# Door_Sensor_Schematic.net
KiCad netlist of a schematic drawn in Altium Designer
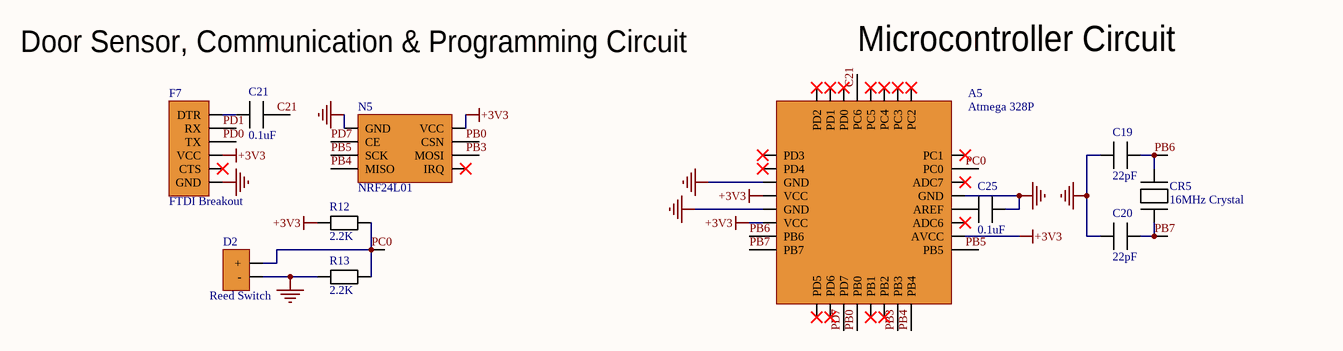
[diagram p0: Door Sensor Schematic.SchDoc]

(export (version "E")
  (design (tool "Eeschema 10.0.6"))
  (components
    (comp (ref "A5")
      (value "Atmega 328P")
      (footprint "ATMega328P")
      (description "IC MCU 8BIT 32KB FLASH 32TQFP")
      (fields
        (field (name "MANUFACTURER") "Microchip")
        (field (name "MANUFACTURER PART NUMBER") "ATMEGA328PB-AUR")
      )
      (libsource (lib "Schematic Library") (part "ATMEGA328PB-AUR"))
    )
    (comp (ref "C19")
      (value "22pF")
      (footprint "22pF Capacitor")
      (description "Cap Ceramic 22pF 50V C0G 5% SMD 0603 125C Paper T/R")
      (fields
        (field (name "MANUFACTURER") "Kyocera AVX")
        (field (name "MANUFACTURER PART NUMBER") "06035A220JAT2A")
      )
      (libsource (lib "Schematic Library") (part "06035A220JAT2A"))
    )
    (comp (ref "C20")
      (value "22pF")
      (footprint "22pF Capacitor")
      (description "Cap Ceramic 22pF 50V C0G 5% SMD 0603 125C Paper T/R")
      (fields
        (field (name "MANUFACTURER") "Kyocera AVX")
        (field (name "MANUFACTURER PART NUMBER") "06035A220JAT2A")
      )
      (libsource (lib "Schematic Library") (part "06035A220JAT2A"))
    )
    (comp (ref "C21")
      (value "0.1uF")
      (footprint "0.1uF Capacitor")
      (description "CAP CER 0.1UF 25V X7R 0603")
      (fields
        (field (name "MANUFACTURER") "Kyocera AVX")
        (field (name "MANUFACTURER PART NUMBER") "06033C104KAT4A")
      )
      (libsource (lib "Schematic Library") (part "06033C104KAT4A"))
    )
    (comp (ref "C25")
      (value "0.1uF")
      (footprint "0.1uF Capacitor")
      (description "CAP CER 0.1UF 25V X7R 0603")
      (fields
        (field (name "MANUFACTURER") "Kyocera AVX")
        (field (name "MANUFACTURER PART NUMBER") "06033C104KAT4A")
      )
      (libsource (lib "Schematic Library") (part "06033C104KAT4A"))
    )
    (comp (ref "CR5")
      (value "16MHz Crystal")
      (footprint "16MHz Crystal")
      (description "CRYSTAL 16.0000MHZ 20PF SMD")
      (fields
        (field (name "MANUFACTURER") "ECS International")
        (field (name "MANUFACTURER PART NUMBER") "ECS-160-20-3X-TR")
      )
      (libsource (lib "Schematic Library") (part "ECS-160-20-3X-TR"))
    )
    (comp (ref "D2")
      (value "Reed Switch")
      (footprint "Reed Switch")
      (description "Magnetic Door Switch Set")
      (fields (field (name "MANUFACTURER") "SparkFun") (field (name "MANUFACTURER PART NUMBER") "COM-13247"))
      (libsource (lib "Schematic Library") (part "COM-13247"))
    )
    (comp (ref "F7")
      (value "FTDI Breakout")
      (footprint "FTDI")
      (description "FTDI USB to TTL serial converter module")
      (libsource (lib "Schematic Library") (part "FTDI"))
    )
    (comp (ref "N5")
      (value "NRF24L01")
      (footprint "NRF24L01")
      (description "3.3V NRF24L01 WIRELESS RF MODULE")
      (libsource (lib "Schematic Library") (part "NRF24L01"))
    )
    (comp (ref "R12")
      (value "2.2K")
      (footprint "2.2K Resistor")
      (description "RES TF 1/10W 2.2K OHM 5% 0603")
      (fields
        (field (name "MANUFACTURER") "Stackpole Electronics")
        (field (name "MANUFACTURER PART NUMBER") "RMCF0603JT2K20")
      )
      (libsource (lib "Schematic Library") (part "RMCF0603JT2K20"))
    )
    (comp (ref "R13")
      (value "2.2K")
      (footprint "2.2K Resistor")
      (description "RES TF 1/10W 2.2K OHM 5% 0603")
      (fields
        (field (name "MANUFACTURER") "Stackpole Electronics")
        (field (name "MANUFACTURER PART NUMBER") "RMCF0603JT2K20")
      )
      (libsource (lib "Schematic Library") (part "RMCF0603JT2K20"))
    )
  )
  (nets
    (net (code "1") (name "+3V3") (class "Default")
      (node (ref "A5") (pin "18") (pinfunction "AVCC_18") (pintype "passive"))
      (node (ref "A5") (pin "4") (pinfunction "VCC_4") (pintype "passive"))
      (node (ref "A5") (pin "6") (pinfunction "VCC_6") (pintype "passive"))
      (node (ref "F7") (pin "4") (pinfunction "VCC_4") (pintype "passive"))
      (node (ref "N5") (pin "5") (pinfunction "VCC_5") (pintype "passive"))
      (node (ref "R12") (pin "2") (pinfunction "2_2") (pintype "passive"))
    )
    (net (code "2") (name "/C21") (class "Default")
      (node (ref "A5") (pin "29") (pinfunction "PC6_29") (pintype "passive"))
      (node (ref "C21") (pin "2") (pinfunction "2_2") (pintype "passive"))
    )
    (net (code "3") (name "/PB0") (class "Default")
      (node (ref "A5") (pin "12") (pinfunction "PB0_12") (pintype "passive"))
      (node (ref "N5") (pin "6") (pinfunction "CSN_6") (pintype "passive"))
    )
    (net (code "4") (name "/PB3") (class "Default")
      (node (ref "A5") (pin "15") (pinfunction "PB3_15") (pintype "passive"))
      (node (ref "N5") (pin "7") (pinfunction "MOSI_7") (pintype "passive"))
    )
    (net (code "5") (name "/PB4") (class "Default")
      (node (ref "A5") (pin "16") (pinfunction "PB4_16") (pintype "passive"))
      (node (ref "N5") (pin "4") (pinfunction "MISO_4") (pintype "passive"))
    )
    (net (code "6") (name "/PB5") (class "Default")
      (node (ref "A5") (pin "17") (pinfunction "PB5_17") (pintype "passive"))
      (node (ref "N5") (pin "3") (pinfunction "SCK_3") (pintype "passive"))
    )
    (net (code "7") (name "/PB6") (class "Default")
      (node (ref "A5") (pin "7") (pinfunction "PB6_7") (pintype "passive"))
      (node (ref "C19") (pin "2") (pinfunction "2_2") (pintype "passive"))
      (node (ref "CR5") (pin "2") (pinfunction "2_2") (pintype "passive"))
    )
    (net (code "8") (name "/PB7") (class "Default")
      (node (ref "A5") (pin "8") (pinfunction "PB7_8") (pintype "passive"))
      (node (ref "C20") (pin "2") (pinfunction "2_2") (pintype "passive"))
      (node (ref "CR5") (pin "1") (pinfunction "1_1") (pintype "passive"))
    )
    (net (code "9") (name "/PC0") (class "Default")
      (node (ref "A5") (pin "23") (pinfunction "PC0_23") (pintype "passive"))
      (node (ref "D2") (pin "2") (pinfunction "+_2") (pintype "passive"))
      (node (ref "R12") (pin "1") (pinfunction "1_1") (pintype "passive"))
      (node (ref "R13") (pin "2") (pinfunction "2_2") (pintype "passive"))
    )
    (net (code "10") (name "/PD0") (class "Default")
      (node (ref "F7") (pin "3") (pinfunction "TX_3") (pintype "passive"))
    )
    (net (code "11") (name "/PD1") (class "Default")
      (node (ref "F7") (pin "2") (pinfunction "RX_2") (pintype "passive"))
    )
    (net (code "12") (name "/PD7") (class "Default")
      (node (ref "A5") (pin "11") (pinfunction "PD7_11") (pintype "passive"))
      (node (ref "N5") (pin "2") (pinfunction "CE_2") (pintype "passive"))
    )
    (net (code "13") (name "GND") (class "Default")
      (node (ref "A5") (pin "21") (pinfunction "GND_21") (pintype "passive"))
      (node (ref "A5") (pin "3") (pinfunction "GND_3") (pintype "passive"))
      (node (ref "A5") (pin "5") (pinfunction "GND_5") (pintype "passive"))
      (node (ref "C19") (pin "1") (pinfunction "1_1") (pintype "passive"))
      (node (ref "C20") (pin "1") (pinfunction "1_1") (pintype "passive"))
      (node (ref "C25") (pin "2") (pinfunction "2_2") (pintype "passive"))
      (node (ref "D2") (pin "1") (pinfunction "-_1") (pintype "passive"))
      (node (ref "F7") (pin "6") (pinfunction "GND_6") (pintype "passive"))
      (node (ref "N5") (pin "1") (pinfunction "GND_1") (pintype "passive"))
      (node (ref "R13") (pin "1") (pinfunction "1_1") (pintype "passive"))
    )
    (net (code "14") (name "Net-(A5-AREF)") (class "Default")
      (node (ref "A5") (pin "20") (pinfunction "AREF_20") (pintype "passive"))
      (node (ref "C25") (pin "1") (pinfunction "1_1") (pintype "passive"))
    )
    (net (code "15") (name "Net-(F7-DTR)") (class "Default")
      (node (ref "C21") (pin "1") (pinfunction "1_1") (pintype "passive"))
      (node (ref "F7") (pin "1") (pinfunction "DTR_1") (pintype "passive"))
    )
    (net (code "16") (name "unconnected-(A5-ADC6-Pad19)") (class "Default")
      (node (ref "A5") (pin "19") (pinfunction "ADC6_19") (pintype "passive+no_connect"))
    )
    (net (code "17") (name "unconnected-(A5-ADC7-Pad22)") (class "Default")
      (node (ref "A5") (pin "22") (pinfunction "ADC7_22") (pintype "passive+no_connect"))
    )
    (net (code "18") (name "unconnected-(A5-PB1-Pad13)") (class "Default")
      (node (ref "A5") (pin "13") (pinfunction "PB1_13") (pintype "passive+no_connect"))
    )
    (net (code "19") (name "unconnected-(A5-PB2-Pad14)") (class "Default")
      (node (ref "A5") (pin "14") (pinfunction "PB2_14") (pintype "passive+no_connect"))
    )
    (net (code "20") (name "unconnected-(A5-PC1-Pad24)") (class "Default")
      (node (ref "A5") (pin "24") (pinfunction "PC1_24") (pintype "passive+no_connect"))
    )
    (net (code "21") (name "unconnected-(A5-PC2-Pad25)") (class "Default")
      (node (ref "A5") (pin "25") (pinfunction "PC2_25") (pintype "passive+no_connect"))
    )
    (net (code "22") (name "unconnected-(A5-PC3-Pad26)") (class "Default")
      (node (ref "A5") (pin "26") (pinfunction "PC3_26") (pintype "passive+no_connect"))
    )
    (net (code "23") (name "unconnected-(A5-PC4-Pad27)") (class "Default")
      (node (ref "A5") (pin "27") (pinfunction "PC4_27") (pintype "passive+no_connect"))
    )
    (net (code "24") (name "unconnected-(A5-PC5-Pad28)") (class "Default")
      (node (ref "A5") (pin "28") (pinfunction "PC5_28") (pintype "passive+no_connect"))
    )
    (net (code "25") (name "unconnected-(A5-PD0-Pad30)") (class "Default")
      (node (ref "A5") (pin "30") (pinfunction "PD0_30") (pintype "passive+no_connect"))
    )
    (net (code "26") (name "unconnected-(A5-PD1-Pad31)") (class "Default")
      (node (ref "A5") (pin "31") (pinfunction "PD1_31") (pintype "passive+no_connect"))
    )
    (net (code "27") (name "unconnected-(A5-PD2-Pad32)") (class "Default")
      (node (ref "A5") (pin "32") (pinfunction "PD2_32") (pintype "passive+no_connect"))
    )
    (net (code "28") (name "unconnected-(A5-PD3-Pad1)") (class "Default")
      (node (ref "A5") (pin "1") (pinfunction "PD3_1") (pintype "passive+no_connect"))
    )
    (net (code "29") (name "unconnected-(A5-PD4-Pad2)") (class "Default")
      (node (ref "A5") (pin "2") (pinfunction "PD4_2") (pintype "passive+no_connect"))
    )
    (net (code "30") (name "unconnected-(A5-PD5-Pad9)") (class "Default")
      (node (ref "A5") (pin "9") (pinfunction "PD5_9") (pintype "passive+no_connect"))
    )
    (net (code "31") (name "unconnected-(A5-PD6-Pad10)") (class "Default")
      (node (ref "A5") (pin "10") (pinfunction "PD6_10") (pintype "passive+no_connect"))
    )
    (net (code "32") (name "unconnected-(F7-CTS-Pad5)") (class "Default")
      (node (ref "F7") (pin "5") (pinfunction "CTS_5") (pintype "passive+no_connect"))
    )
    (net (code "33") (name "unconnected-(N5-IRQ-Pad8)") (class "Default")
      (node (ref "N5") (pin "8") (pinfunction "IRQ_8") (pintype "passive+no_connect"))
    )
  )
)
